# programmer.net
KiCad netlist of a schematic drawn in Altium Designer
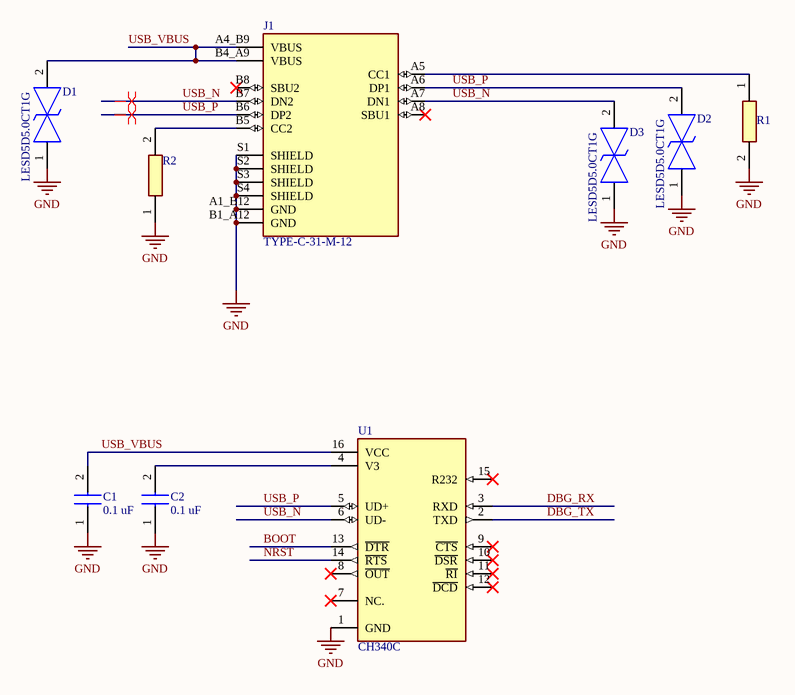
[diagram p0: programmer.SchDoc]

(export (version "E")
  (design (tool "Eeschema 10.0.6"))
  (components
    (comp (ref "C1")
      (value "0.1 uF")
      (footprint "CAP0603")
      (description "Capacitor")
      (fields
        (field (name "MANUFACTURER_PART_NUMBER") "CC0603KRX7R9BB104")
        (field (name "MOUSER PART NUMBER") "603-CC603KRX7R9BB104")
      )
      (libsource (lib "Valve_Controller_Lib") (part "CC0603KRX7R9BB104"))
    )
    (comp (ref "C2")
      (value "0.1 uF")
      (footprint "CAP0603")
      (description "Capacitor")
      (fields
        (field (name "MANUFACTURER_PART_NUMBER") "CC0603KRX7R9BB104")
        (field (name "MOUSER PART NUMBER") "603-CC603KRX7R9BB104")
      )
      (libsource (lib "Valve_Controller_Lib") (part "CC0603KRX7R9BB104"))
    )
    (comp (ref "D1")
      (value "LESD5D5.0CT1G")
      (footprint "SamacSys:LESD5D50CT1G")
      (description "TVS Diode (Bi-directional)")
      (libsource (lib "*") (part "LESD5D5.0CT1G"))
    )
    (comp (ref "D2")
      (value "LESD5D5.0CT1G")
      (footprint "SamacSys:LESD5D50CT1G")
      (description "TVS Diode (Bi-directional)")
      (libsource (lib "*") (part "LESD5D5.0CT1G"))
    )
    (comp (ref "D3")
      (value "LESD5D5.0CT1G")
      (footprint "SamacSys:LESD5D50CT1G")
      (description "TVS Diode (Bi-directional)")
      (libsource (lib "*") (part "LESD5D5.0CT1G"))
    )
    (comp (ref "J1")
      (value "TYPE-C-31-M-12")
      (footprint "HRO_TYPE-C-31-M-12")
      (description "USB Connectors 24 Receptacle 1 8.94*7.3mm RoHS")
      (fields (field (name "MF") "HRO Electronics Co., Ltd."))
      (libsource (lib "TYPE-C-31-M-12") (part "TYPE-C-31-M-12"))
    )
    (comp (ref "R1")
      (value "CRCW0402100KFKEDHP")
      (footprint "RESC1005X40N")
      (description "Resistor")
      (fields (field (name "MOUSER PART NUMBER") "71-CRCW0402100KFKEDH"))
      (libsource (lib "") (part "CRCW0402100KFKEDHP_1"))
    )
    (comp (ref "R2")
      (value "CRCW0402100KFKEDHP")
      (footprint "RESC1005X40N")
      (description "Resistor")
      (fields (field (name "MOUSER PART NUMBER") "71-CRCW0402100KFKEDH"))
      (libsource (lib "Valve_Controller_Lib") (part "CRCW0402100KFKEDHP"))
    )
    (comp (ref "U1")
      (value "CH340C")
      (footprint "SOIC127P600X180-16N")
      (description "USB to serial chip CH340")
      (fields (field (name "MF") "WCH"))
      (libsource (lib "CH340C") (part "CH340C"))
    )
  )
  (nets
    (net (code "1") (name "/BOOT") (class "Default")
      (node (ref "U1") (pin "13") (pinfunction "~{DTR}_13") (pintype "output"))
    )
    (net (code "2") (name "/DBG_RX") (class "Default")
      (node (ref "U1") (pin "3") (pinfunction "RXD_3") (pintype "input"))
    )
    (net (code "3") (name "/DBG_TX") (class "Default")
      (node (ref "U1") (pin "2") (pinfunction "TXD_2") (pintype "output"))
    )
    (net (code "4") (name "/NRST") (class "Default")
      (node (ref "U1") (pin "14") (pinfunction "~{RTS}_14") (pintype "output"))
    )
    (net (code "5") (name "/USB_N") (class "Default")
      (node (ref "D3") (pin "2") (pinfunction "2_2") (pintype "passive"))
      (node (ref "J1") (pin "A7") (pinfunction "DN1_A7") (pintype "bidirectional"))
      (node (ref "J1") (pin "B7") (pinfunction "DN2_B7") (pintype "bidirectional"))
      (node (ref "U1") (pin "6") (pinfunction "UD-_6") (pintype "bidirectional"))
    )
    (net (code "6") (name "/USB_P") (class "Default")
      (node (ref "D2") (pin "2") (pinfunction "2_2") (pintype "passive"))
      (node (ref "J1") (pin "A6") (pinfunction "DP1_A6") (pintype "bidirectional"))
      (node (ref "J1") (pin "B6") (pinfunction "DP2_B6") (pintype "bidirectional"))
      (node (ref "U1") (pin "5") (pinfunction "UD+_5") (pintype "bidirectional"))
    )
    (net (code "7") (name "/USB_VBUS") (class "Default")
      (node (ref "C1") (pin "2") (pinfunction "2_2") (pintype "passive"))
      (node (ref "D1") (pin "2") (pinfunction "2_2") (pintype "passive"))
      (node (ref "J1") (pin "A4_B9") (pinfunction "VBUS_A4_B9") (pintype "power_in"))
      (node (ref "J1") (pin "B4_A9") (pinfunction "VBUS_B4_A9") (pintype "power_in"))
      (node (ref "U1") (pin "16") (pinfunction "VCC_16") (pintype "power_in"))
    )
    (net (code "8") (name "GND") (class "Default")
      (node (ref "C1") (pin "1") (pinfunction "1_1") (pintype "passive"))
      (node (ref "C2") (pin "1") (pinfunction "1_1") (pintype "passive"))
      (node (ref "D1") (pin "1") (pinfunction "1_1") (pintype "passive"))
      (node (ref "D2") (pin "1") (pinfunction "1_1") (pintype "passive"))
      (node (ref "D3") (pin "1") (pinfunction "1_1") (pintype "passive"))
      (node (ref "J1") (pin "A1_B12") (pinfunction "GND_A1_B12") (pintype "power_in"))
      (node (ref "J1") (pin "B1_A12") (pinfunction "GND_B1_A12") (pintype "power_in"))
      (node (ref "J1") (pin "S1") (pinfunction "SHIELD_S1") (pintype "passive"))
      (node (ref "J1") (pin "S2") (pinfunction "SHIELD_S2") (pintype "passive"))
      (node (ref "J1") (pin "S3") (pinfunction "SHIELD_S3") (pintype "passive"))
      (node (ref "J1") (pin "S4") (pinfunction "SHIELD_S4") (pintype "passive"))
      (node (ref "R1") (pin "2") (pinfunction "2_2") (pintype "passive"))
      (node (ref "R2") (pin "1") (pinfunction "1_1") (pintype "passive"))
      (node (ref "U1") (pin "1") (pinfunction "GND_1") (pintype "power_in"))
    )
    (net (code "9") (name "Net-(J1-CC1)") (class "Default")
      (node (ref "J1") (pin "A5") (pinfunction "CC1_A5") (pintype "bidirectional"))
      (node (ref "R1") (pin "1") (pinfunction "1_1") (pintype "passive"))
    )
    (net (code "10") (name "Net-(J1-CC2)") (class "Default")
      (node (ref "J1") (pin "B5") (pinfunction "CC2_B5") (pintype "bidirectional"))
      (node (ref "R2") (pin "2") (pinfunction "2_2") (pintype "passive"))
    )
    (net (code "11") (name "Net-(U1-V3)") (class "Default")
      (node (ref "C2") (pin "2") (pinfunction "2_2") (pintype "passive"))
      (node (ref "U1") (pin "4") (pinfunction "V3_4") (pintype "power_in"))
    )
    (net (code "12") (name "unconnected-(J1-SBU1-PadA8)") (class "Default")
      (node (ref "J1") (pin "A8") (pinfunction "SBU1_A8") (pintype "bidirectional+no_connect"))
    )
    (net (code "13") (name "unconnected-(J1-SBU2-PadB8)") (class "Default")
      (node (ref "J1") (pin "B8") (pinfunction "SBU2_B8") (pintype "bidirectional+no_connect"))
    )
    (net (code "14") (name "unconnected-(U1-NC.-Pad7)") (class "Default")
      (node (ref "U1") (pin "7") (pinfunction "NC._7") (pintype "passive+no_connect"))
    )
    (net (code "15") (name "unconnected-(U1-R232-Pad15)") (class "Default")
      (node (ref "U1") (pin "15") (pinfunction "R232_15") (pintype "input+no_connect"))
    )
    (net (code "16") (name "unconnected-(U1-~{CTS}-Pad9)") (class "Default")
      (node (ref "U1") (pin "9") (pinfunction "~{CTS}_9") (pintype "input+no_connect"))
    )
    (net (code "17") (name "unconnected-(U1-~{DCD}-Pad12)") (class "Default")
      (node (ref "U1") (pin "12") (pinfunction "~{DCD}_12") (pintype "input+no_connect"))
    )
    (net (code "18") (name "unconnected-(U1-~{DSR}-Pad10)") (class "Default")
      (node (ref "U1") (pin "10") (pinfunction "~{DSR}_10") (pintype "input+no_connect"))
    )
    (net (code "19") (name "unconnected-(U1-~{OUT}-Pad8)") (class "Default")
      (node (ref "U1") (pin "8") (pinfunction "~{OUT}_8") (pintype "output+no_connect"))
    )
    (net (code "20") (name "unconnected-(U1-~{RI}-Pad11)") (class "Default")
      (node (ref "U1") (pin "11") (pinfunction "~{RI}_11") (pintype "input+no_connect"))
    )
  )
)
